# remoter.net
KiCad netlist of a schematic drawn in Altium Designer
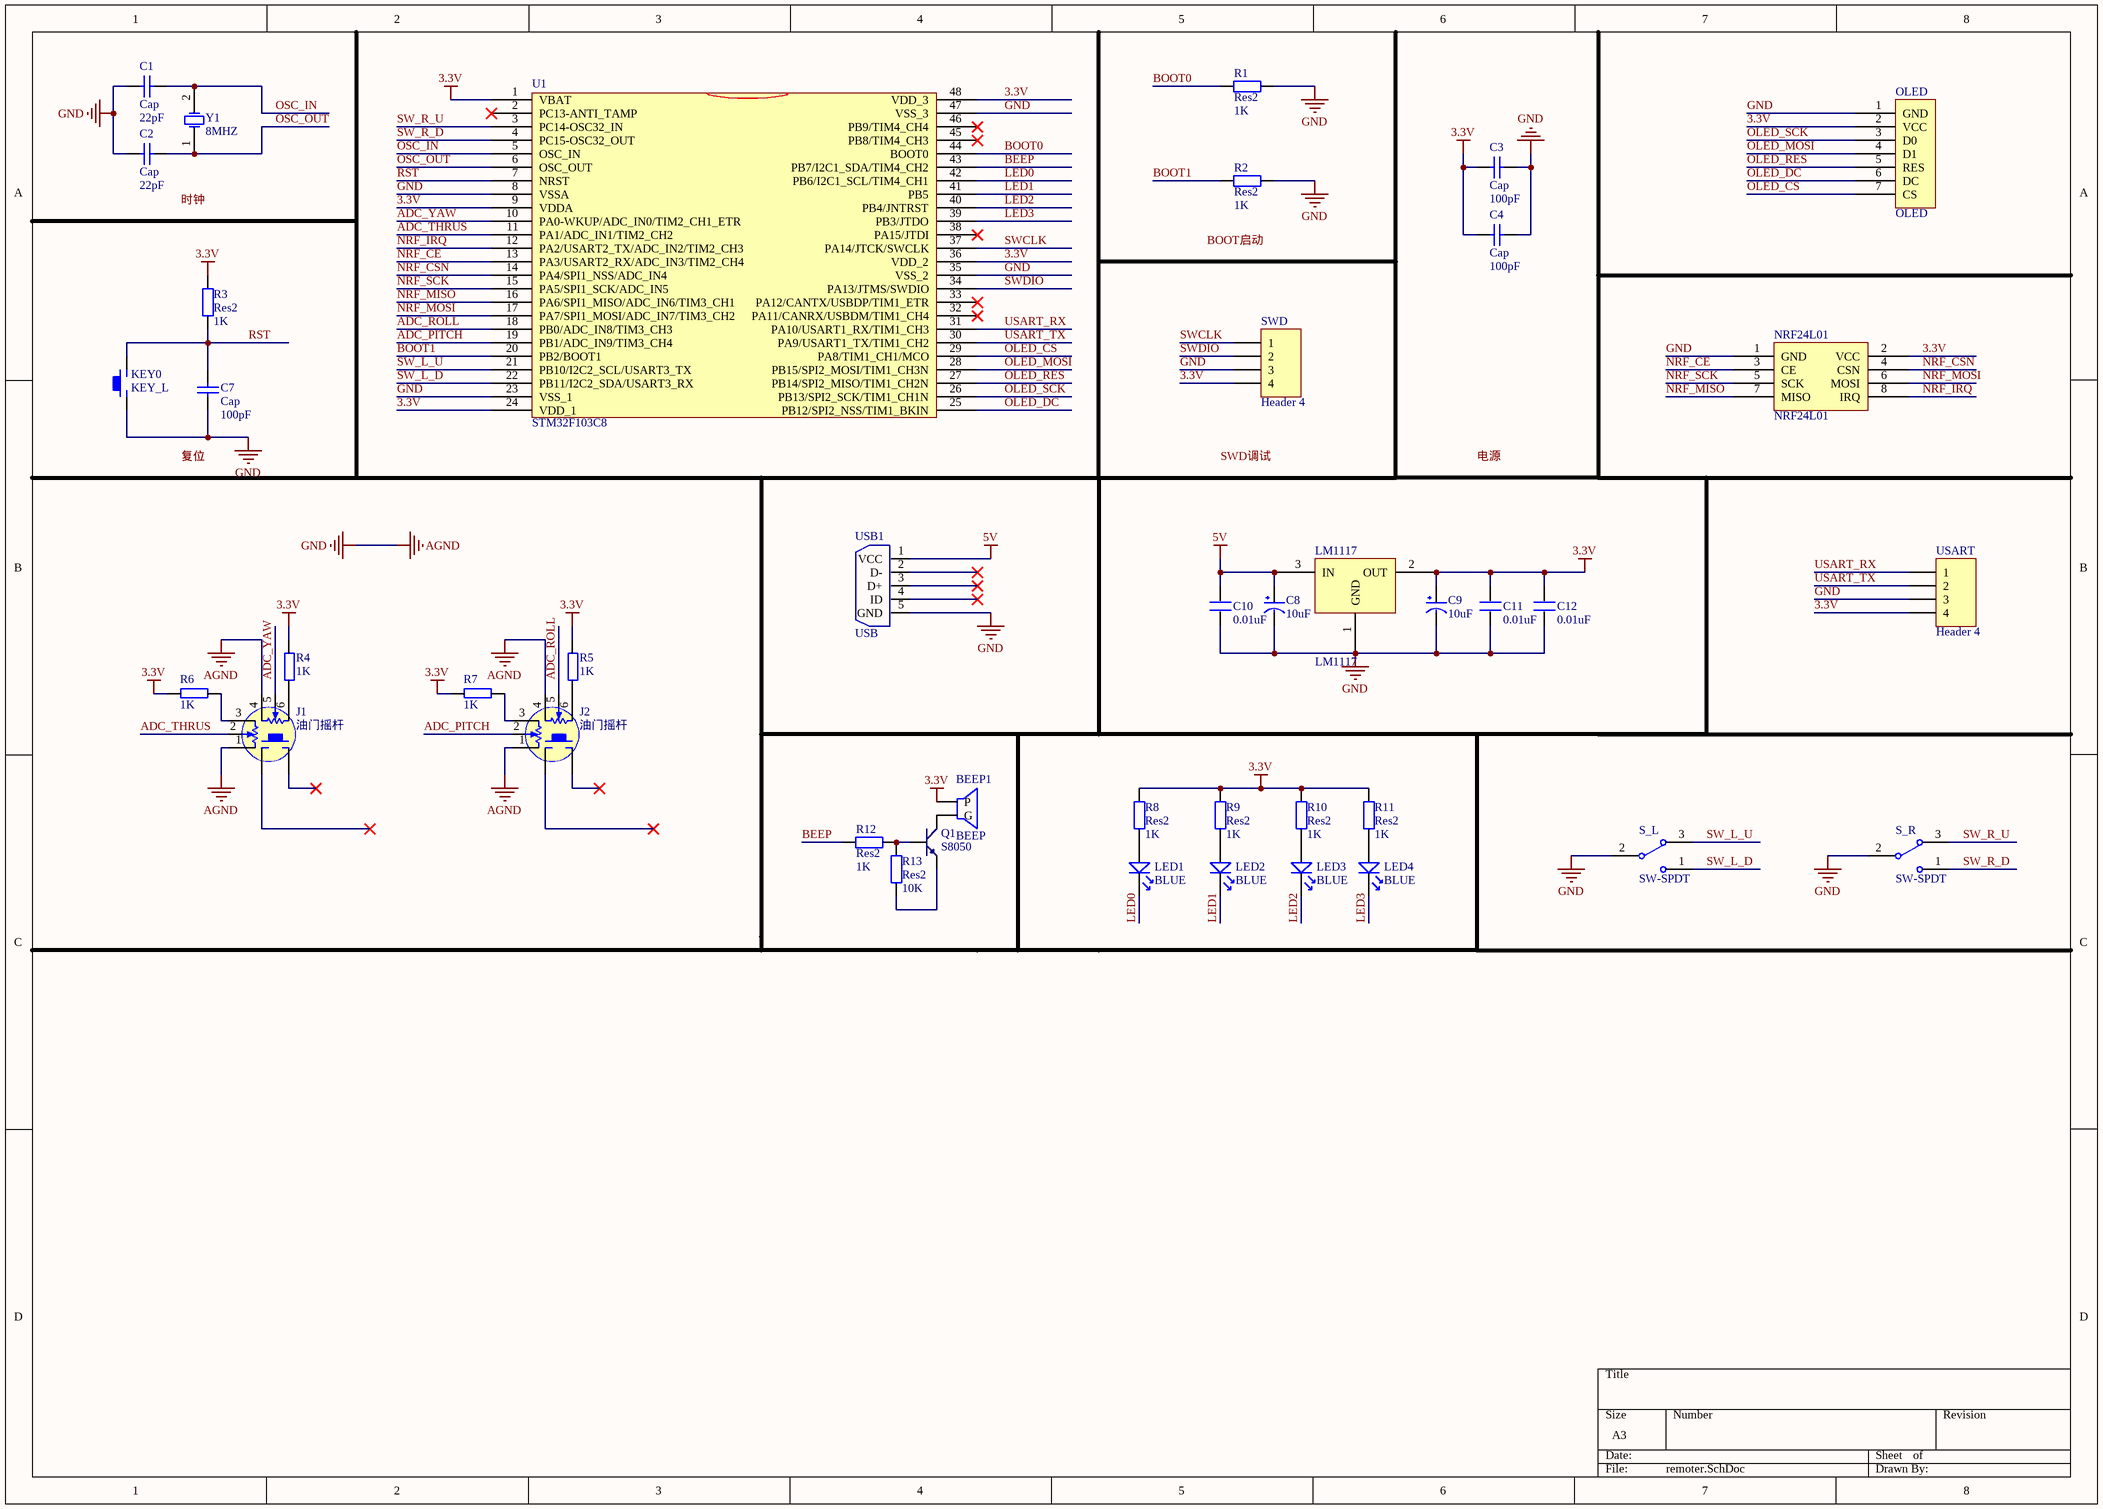
[diagram p0: remoter.SchDoc]

(export (version "E")
  (design (tool "Eeschema 10.0.6"))
  (components
    (comp (ref "BEEP1") (value "BEEP") (footprint "BELL-5") (libsource (lib "REMOTOR V1.6") (part "BEEP")))
    (comp (ref "C1")
      (value "Cap")
      (footprint "0805")
      (description "Capacitor")
      (fields (field (name "ALTIUM_VALUE") "22pF") (field (name "PUBLISHER") "Altium Limited"))
      (libsource (lib "Miscellaneous Devices") (part "Cap"))
    )
    (comp (ref "C2")
      (value "Cap")
      (footprint "0805")
      (description "Capacitor")
      (fields (field (name "ALTIUM_VALUE") "22pF") (field (name "PUBLISHER") "Altium Limited"))
      (libsource (lib "Miscellaneous Devices") (part "Cap"))
    )
    (comp (ref "C3")
      (value "Cap")
      (footprint "0805")
      (description "Capacitor")
      (fields (field (name "ALTIUM_VALUE") "100pF") (field (name "PUBLISHER") "Altium Limited"))
      (libsource (lib "Miscellaneous Devices") (part "Cap"))
    )
    (comp (ref "C4")
      (value "Cap")
      (footprint "0805")
      (description "Capacitor")
      (fields (field (name "ALTIUM_VALUE") "100pF") (field (name "PUBLISHER") "Altium Limited"))
      (libsource (lib "Miscellaneous Devices") (part "Cap"))
    )
    (comp (ref "C7")
      (value "Cap")
      (footprint "0805")
      (description "Capacitor")
      (fields (field (name "ALTIUM_VALUE") "100pF") (field (name "PUBLISHER") "Altium Limited"))
      (libsource (lib "Miscellaneous Devices") (part "Cap"))
    )
    (comp (ref "C8") (value "10uF") (footprint "C1206") (libsource (lib "REMOTOR V1.6") (part "CAP")))
    (comp (ref "C9") (value "10uF") (footprint "C1206") (libsource (lib "REMOTOR V1.6") (part "CAP")))
    (comp (ref "C10") (value "0.01uF") (footprint "0805") (libsource (lib "REMOTOR V1.6") (part "C")))
    (comp (ref "C11") (value "0.01uF") (footprint "0805") (libsource (lib "REMOTOR V1.6") (part "C")))
    (comp (ref "C12") (value "0.01uF") (footprint "0805") (libsource (lib "REMOTOR V1.6") (part "C")))
    (comp (ref "J1")
      (value "油门摇杆")
      (footprint "摇杆2")
      (description "摇杆")
      (libsource (lib "REMOTOR V1.6") (part "摇杆"))
    )
    (comp (ref "J2")
      (value "油门摇杆")
      (footprint "摇杆2")
      (description "摇杆")
      (libsource (lib "REMOTOR V1.6") (part "摇杆"))
    )
    (comp (ref "KEY0") (value "KEY_L") (footprint "KEY_M") (libsource (lib "REMOTOR V1.6") (part "KEY")))
    (comp (ref "LED1") (value "BLUE") (footprint "0805") (libsource (lib "REMOTOR V1.6") (part "LED")))
    (comp (ref "LED2") (value "BLUE") (footprint "0805") (libsource (lib "REMOTOR V1.6") (part "LED")))
    (comp (ref "LED3") (value "BLUE") (footprint "0805") (libsource (lib "REMOTOR V1.6") (part "LED")))
    (comp (ref "LED4") (value "BLUE") (footprint "0805") (libsource (lib "REMOTOR V1.6") (part "LED")))
    (comp (ref "LM1117")
      (value "LM1117")
      (description "线性稳压3.3V")
      (libsource (lib "Remoschlib") (part "LM1117"))
    )
    (comp (ref "NRF24L01")
      (value "NRF24L01")
      (footprint "HDR2X4")
      (libsource (lib "Remoschlib") (part "NRF24L01"))
    )
    (comp (ref "OLED") (value "OLED") (footprint "HDR1X7") (libsource (lib "Remoschlib") (part "OLED")))
    (comp (ref "Q1")
      (value "S8050")
      (footprint "SOT-23R")
      (description "8050/BCW846/BCW847")
      (libsource (lib "REMOTOR V1.6") (part "NPN"))
    )
    (comp (ref "R1")
      (value "Res2")
      (footprint "0805")
      (description "Resistor")
      (fields (field (name "ALTIUM_VALUE") "1K") (field (name "PUBLISHER") "Altium Limited"))
      (libsource (lib "") (part "Res2_2"))
    )
    (comp (ref "R2")
      (value "Res2")
      (footprint "0805")
      (description "Resistor")
      (fields (field (name "ALTIUM_VALUE") "1K") (field (name "PUBLISHER") "Altium Limited"))
      (libsource (lib "Miscellaneous Devices") (part "Res2"))
    )
    (comp (ref "R3")
      (value "Res2")
      (footprint "0805")
      (description "Resistor")
      (fields (field (name "ALTIUM_VALUE") "1K") (field (name "PUBLISHER") "Altium Limited"))
      (libsource (lib "") (part "Res2_1"))
    )
    (comp (ref "R4") (value "1K") (footprint "0805") (libsource (lib "REMOTOR V1.6") (part "R")))
    (comp (ref "R5") (value "1K") (footprint "0805") (libsource (lib "REMOTOR V1.6") (part "R")))
    (comp (ref "R6") (value "1K") (footprint "0805") (libsource (lib "REMOTOR V1.6") (part "R")))
    (comp (ref "R7") (value "1K") (footprint "0805") (libsource (lib "REMOTOR V1.6") (part "R")))
    (comp (ref "R8")
      (value "Res2")
      (footprint "0805")
      (description "Resistor")
      (fields (field (name "ALTIUM_VALUE") "1K") (field (name "PUBLISHER") "Altium Limited"))
      (libsource (lib "") (part "Res2_1"))
    )
    (comp (ref "R9")
      (value "Res2")
      (footprint "0805")
      (description "Resistor")
      (fields (field (name "ALTIUM_VALUE") "1K") (field (name "PUBLISHER") "Altium Limited"))
      (libsource (lib "") (part "Res2_1"))
    )
    (comp (ref "R10")
      (value "Res2")
      (footprint "0805")
      (description "Resistor")
      (fields (field (name "ALTIUM_VALUE") "1K") (field (name "PUBLISHER") "Altium Limited"))
      (libsource (lib "") (part "Res2_1"))
    )
    (comp (ref "R11")
      (value "Res2")
      (footprint "0805")
      (description "Resistor")
      (fields (field (name "ALTIUM_VALUE") "1K") (field (name "PUBLISHER") "Altium Limited"))
      (libsource (lib "") (part "Res2_1"))
    )
    (comp (ref "R12")
      (value "Res2")
      (footprint "0805")
      (description "Resistor")
      (fields (field (name "ALTIUM_VALUE") "1K") (field (name "PUBLISHER") "Altium Limited"))
      (libsource (lib "Miscellaneous Devices") (part "Res2"))
    )
    (comp (ref "R13")
      (value "Res2")
      (footprint "0805")
      (description "Resistor")
      (fields (field (name "ALTIUM_VALUE") "10K") (field (name "PUBLISHER") "Altium Limited"))
      (libsource (lib "") (part "Res2_1"))
    )
    (comp (ref "SWD")
      (value "Header 4")
      (footprint "HDR1X4")
      (description "Header, 4-Pin")
      (fields (field (name "PUBLISHER") "Altium Limited"))
      (libsource (lib "Miscellaneous Connectors") (part "Header 4"))
    )
    (comp (ref "S_L")
      (value "SW-SPDT")
      (footprint "扭子开关")
      (description "SPDT Subminiature Toggle Switch, Right Angle Mounting, Vertical Actuation")
      (fields (field (name "PUBLISHER") "Altium Limited"))
      (libsource (lib "Miscellaneous Devices") (part "SW-SPDT"))
    )
    (comp (ref "S_R")
      (value "SW-SPDT")
      (footprint "扭子开关")
      (description "SPDT Subminiature Toggle Switch, Right Angle Mounting, Vertical Actuation")
      (fields (field (name "PUBLISHER") "Altium Limited"))
      (libsource (lib "Miscellaneous Devices") (part "SW-SPDT"))
    )
    (comp (ref "U1")
      (value "STM32F103C8")
      (footprint "mTQFP48")
      (libsource (lib "REMOTOR V1.6") (part "STM32F103C6"))
    )
    (comp (ref "USART")
      (value "Header 4")
      (footprint "HDR1X4")
      (description "Header, 4-Pin")
      (fields (field (name "PUBLISHER") "Altium Limited"))
      (libsource (lib "Miscellaneous Connectors") (part "Header 4"))
    )
    (comp (ref "USB1")
      (value "USB")
      (footprint "MICROUSB-SOP")
      (libsource (lib "REMOTOR V1.6") (part "USB5"))
    )
    (comp (ref "Y1")
      (value "8MHZ")
      (footprint "XTAL3225   无源")
      (description "Crystal Oscillator")
      (fields (field (name "PUBLISHER") "Altium Limited"))
      (libsource (lib "Miscellaneous Devices") (part "XTAL"))
    )
  )
  (nets
    (net (code "1") (name "/ADC_PITCH") (class "Default")
      (node (ref "J2") (pin "2") (pinfunction "2_2") (pintype "passive"))
      (node (ref "U1") (pin "19") (pinfunction "PB1/ADC_IN9/TIM3_CH4_19") (pintype "passive"))
    )
    (net (code "2") (name "/ADC_ROLL") (class "Default")
      (node (ref "J2") (pin "5") (pinfunction "5_5") (pintype "passive"))
      (node (ref "U1") (pin "18") (pinfunction "PB0/ADC_IN8/TIM3_CH3_18") (pintype "passive"))
    )
    (net (code "3") (name "/ADC_THRUS") (class "Default")
      (node (ref "J1") (pin "2") (pinfunction "2_2") (pintype "passive"))
      (node (ref "U1") (pin "11") (pinfunction "PA1/ADC_IN1/TIM2_CH2_11") (pintype "passive"))
    )
    (net (code "4") (name "/ADC_YAW") (class "Default")
      (node (ref "J1") (pin "5") (pinfunction "5_5") (pintype "passive"))
      (node (ref "U1") (pin "10") (pinfunction "PA0-WKUP/ADC_IN0/TIM2_CH1_ETR_10") (pintype "passive"))
    )
    (net (code "5") (name "/BEEP") (class "Default")
      (node (ref "R12") (pin "2") (pinfunction "2_2") (pintype "passive"))
      (node (ref "U1") (pin "43") (pinfunction "PB7/I2C1_SDA/TIM4_CH2_43") (pintype "passive"))
    )
    (net (code "6") (name "/BOOT0") (class "Default")
      (node (ref "R1") (pin "1") (pinfunction "1_1") (pintype "passive"))
      (node (ref "U1") (pin "44") (pinfunction "BOOT0_44") (pintype "passive"))
    )
    (net (code "7") (name "/BOOT1") (class "Default")
      (node (ref "R2") (pin "2") (pinfunction "2_2") (pintype "passive"))
      (node (ref "U1") (pin "20") (pinfunction "PB2/BOOT1_20") (pintype "passive"))
    )
    (net (code "8") (name "/LED0") (class "Default")
      (node (ref "LED1") (pin "2") (pinfunction "2_2") (pintype "passive"))
      (node (ref "U1") (pin "42") (pinfunction "PB6/I2C1_SCL/TIM4_CH1_42") (pintype "passive"))
    )
    (net (code "9") (name "/LED1") (class "Default")
      (node (ref "LED2") (pin "2") (pinfunction "2_2") (pintype "passive"))
      (node (ref "U1") (pin "41") (pinfunction "PB5_41") (pintype "passive"))
    )
    (net (code "10") (name "/LED2") (class "Default")
      (node (ref "LED3") (pin "2") (pinfunction "2_2") (pintype "passive"))
      (node (ref "U1") (pin "40") (pinfunction "PB4/JNTRST_40") (pintype "passive"))
    )
    (net (code "11") (name "/LED3") (class "Default")
      (node (ref "LED4") (pin "2") (pinfunction "2_2") (pintype "passive"))
      (node (ref "U1") (pin "39") (pinfunction "PB3/JTDO_39") (pintype "passive"))
    )
    (net (code "12") (name "/NRF_CE") (class "Default")
      (node (ref "NRF24L01") (pin "3") (pinfunction "CE_3") (pintype "passive"))
      (node (ref "U1") (pin "13") (pinfunction "PA3/USART2_RX/ADC_IN3/TIM2_CH4_13") (pintype "passive"))
    )
    (net (code "13") (name "/NRF_CSN") (class "Default")
      (node (ref "NRF24L01") (pin "4") (pinfunction "CSN_4") (pintype "passive"))
      (node (ref "U1") (pin "14") (pinfunction "PA4/SPI1_NSS/ADC_IN4_14") (pintype "passive"))
    )
    (net (code "14") (name "/NRF_IRQ") (class "Default")
      (node (ref "NRF24L01") (pin "8") (pinfunction "IRQ_8") (pintype "passive"))
      (node (ref "U1") (pin "12") (pinfunction "PA2/USART2_TX/ADC_IN2/TIM2_CH3_12") (pintype "passive"))
    )
    (net (code "15") (name "/NRF_MISO") (class "Default")
      (node (ref "NRF24L01") (pin "7") (pinfunction "MISO_7") (pintype "passive"))
      (node (ref "U1") (pin "16") (pinfunction "PA6/SPI1_MISO/ADC_IN6/TIM3_CH1_16") (pintype "passive"))
    )
    (net (code "16") (name "/NRF_MOSI") (class "Default")
      (node (ref "NRF24L01") (pin "6") (pinfunction "MOSI_6") (pintype "passive"))
      (node (ref "U1") (pin "17") (pinfunction "PA7/SPI1_MOSI/ADC_IN7/TIM3_CH2_17") (pintype "passive"))
    )
    (net (code "17") (name "/NRF_SCK") (class "Default")
      (node (ref "NRF24L01") (pin "5") (pinfunction "SCK_5") (pintype "passive"))
      (node (ref "U1") (pin "15") (pinfunction "PA5/SPI1_SCK/ADC_IN5_15") (pintype "passive"))
    )
    (net (code "18") (name "/OLED_CS") (class "Default")
      (node (ref "OLED") (pin "7") (pinfunction "CS_7") (pintype "passive"))
      (node (ref "U1") (pin "29") (pinfunction "PA8/TIM1_CH1/MCO_29") (pintype "passive"))
    )
    (net (code "19") (name "/OLED_DC") (class "Default")
      (node (ref "OLED") (pin "6") (pinfunction "DC_6") (pintype "passive"))
      (node (ref "U1") (pin "25") (pinfunction "PB12/SPI2_NSS/TIM1_BKIN_25") (pintype "passive"))
    )
    (net (code "20") (name "/OLED_MOSI") (class "Default")
      (node (ref "OLED") (pin "4") (pinfunction "D1_4") (pintype "passive"))
      (node (ref "U1") (pin "28") (pinfunction "PB15/SPI2_MOSI/TIM1_CH3N_28") (pintype "passive"))
    )
    (net (code "21") (name "/OLED_RES") (class "Default")
      (node (ref "OLED") (pin "5") (pinfunction "RES_5") (pintype "passive"))
      (node (ref "U1") (pin "27") (pinfunction "PB14/SPI2_MISO/TIM1_CH2N_27") (pintype "passive"))
    )
    (net (code "22") (name "/OLED_SCK") (class "Default")
      (node (ref "OLED") (pin "3") (pinfunction "D0_3") (pintype "passive"))
      (node (ref "U1") (pin "26") (pinfunction "PB13/SPI2_SCK/TIM1_CH1N_26") (pintype "passive"))
    )
    (net (code "23") (name "/OSC_IN") (class "Default")
      (node (ref "C1") (pin "2") (pinfunction "2_2") (pintype "passive"))
      (node (ref "U1") (pin "5") (pinfunction "OSC_IN_5") (pintype "passive"))
      (node (ref "Y1") (pin "2") (pinfunction "OSC2_2") (pintype "passive"))
    )
    (net (code "24") (name "/OSC_OUT") (class "Default")
      (node (ref "C2") (pin "2") (pinfunction "2_2") (pintype "passive"))
      (node (ref "U1") (pin "6") (pinfunction "OSC_OUT_6") (pintype "passive"))
      (node (ref "Y1") (pin "1") (pinfunction "OSC1_1") (pintype "passive"))
    )
    (net (code "25") (name "/RST") (class "Default")
      (node (ref "C7") (pin "2") (pinfunction "2_2") (pintype "passive"))
      (node (ref "KEY0") (pin "2") (pinfunction "2_2") (pintype "passive"))
      (node (ref "R3") (pin "1") (pinfunction "1_1") (pintype "passive"))
      (node (ref "U1") (pin "7") (pinfunction "NRST_7") (pintype "passive"))
    )
    (net (code "26") (name "/SWCLK") (class "Default")
      (node (ref "SWD") (pin "1") (pinfunction "1_1") (pintype "passive"))
      (node (ref "U1") (pin "37") (pinfunction "PA14/JTCK/SWCLK_37") (pintype "passive"))
    )
    (net (code "27") (name "/SWDIO") (class "Default")
      (node (ref "SWD") (pin "2") (pinfunction "2_2") (pintype "passive"))
      (node (ref "U1") (pin "34") (pinfunction "PA13/JTMS/SWDIO_34") (pintype "passive"))
    )
    (net (code "28") (name "/SW_L_D") (class "Default")
      (node (ref "S_L") (pin "1") (pinfunction "1_1") (pintype "passive"))
      (node (ref "U1") (pin "22") (pinfunction "PB11/I2C2_SDA/USART3_RX_22") (pintype "passive"))
    )
    (net (code "29") (name "/SW_L_U") (class "Default")
      (node (ref "S_L") (pin "3") (pinfunction "3_3") (pintype "passive"))
      (node (ref "U1") (pin "21") (pinfunction "PB10/I2C2_SCL/USART3_TX_21") (pintype "passive"))
    )
    (net (code "30") (name "/SW_R_D") (class "Default")
      (node (ref "S_R") (pin "1") (pinfunction "1_1") (pintype "passive"))
      (node (ref "U1") (pin "4") (pinfunction "PC15-OSC32_OUT_4") (pintype "passive"))
    )
    (net (code "31") (name "/SW_R_U") (class "Default")
      (node (ref "S_R") (pin "3") (pinfunction "3_3") (pintype "passive"))
      (node (ref "U1") (pin "3") (pinfunction "PC14-OSC32_IN_3") (pintype "passive"))
    )
    (net (code "32") (name "/USART_RX") (class "Default")
      (node (ref "U1") (pin "31") (pinfunction "PA10/USART1_RX/TIM1_CH3_31") (pintype "passive"))
      (node (ref "USART") (pin "1") (pinfunction "1_1") (pintype "passive"))
    )
    (net (code "33") (name "/USART_TX") (class "Default")
      (node (ref "U1") (pin "30") (pinfunction "PA9/USART1_TX/TIM1_CH2_30") (pintype "passive"))
      (node (ref "USART") (pin "2") (pinfunction "2_2") (pintype "passive"))
    )
    (net (code "34") (name "3.3V") (class "Default")
      (node (ref "BEEP1") (pin "1") (pinfunction "P_1") (pintype "passive"))
      (node (ref "C11") (pin "2") (pintype "passive"))
      (node (ref "C12") (pin "2") (pintype "passive"))
      (node (ref "C3") (pin "1") (pinfunction "1_1") (pintype "passive"))
      (node (ref "C4") (pin "1") (pinfunction "1_1") (pintype "passive"))
      (node (ref "C9") (pin "1") (pinfunction "VCC_1") (pintype "passive"))
      (node (ref "LM1117") (pin "2") (pinfunction "OUT_2") (pintype "passive"))
      (node (ref "NRF24L01") (pin "2") (pinfunction "VCC_2") (pintype "passive"))
      (node (ref "OLED") (pin "2") (pinfunction "VCC_2") (pintype "passive"))
      (node (ref "R10") (pin "2") (pinfunction "2_2") (pintype "passive"))
      (node (ref "R11") (pin "2") (pinfunction "2_2") (pintype "passive"))
      (node (ref "R3") (pin "2") (pinfunction "2_2") (pintype "passive"))
      (node (ref "R4") (pin "2") (pintype "passive"))
      (node (ref "R5") (pin "2") (pintype "passive"))
      (node (ref "R6") (pin "2") (pintype "passive"))
      (node (ref "R7") (pin "2") (pintype "passive"))
      (node (ref "R8") (pin "2") (pinfunction "2_2") (pintype "passive"))
      (node (ref "R9") (pin "2") (pinfunction "2_2") (pintype "passive"))
      (node (ref "SWD") (pin "4") (pinfunction "4_4") (pintype "passive"))
      (node (ref "U1") (pin "1") (pinfunction "VBAT_1") (pintype "passive"))
      (node (ref "U1") (pin "24") (pinfunction "VDD_1_24") (pintype "passive"))
      (node (ref "U1") (pin "36") (pinfunction "VDD_2_36") (pintype "passive"))
      (node (ref "U1") (pin "48") (pinfunction "VDD_3_48") (pintype "passive"))
      (node (ref "U1") (pin "9") (pinfunction "VDDA_9") (pintype "passive"))
      (node (ref "USART") (pin "4") (pinfunction "4_4") (pintype "passive"))
    )
    (net (code "35") (name "5V") (class "Default")
      (node (ref "C10") (pin "2") (pintype "passive"))
      (node (ref "C8") (pin "1") (pinfunction "VCC_1") (pintype "passive"))
      (node (ref "LM1117") (pin "3") (pinfunction "IN_3") (pintype "passive"))
      (node (ref "USB1") (pin "1") (pinfunction "VCC_1") (pintype "passive"))
    )
    (net (code "36") (name "AGND") (class "Default")
      (node (ref "C1") (pin "1") (pinfunction "1_1") (pintype "passive"))
      (node (ref "C10") (pin "1") (pintype "passive"))
      (node (ref "C11") (pin "1") (pintype "passive"))
      (node (ref "C12") (pin "1") (pintype "passive"))
      (node (ref "C2") (pin "1") (pinfunction "1_1") (pintype "passive"))
      (node (ref "C3") (pin "2") (pinfunction "2_2") (pintype "passive"))
      (node (ref "C4") (pin "2") (pinfunction "2_2") (pintype "passive"))
      (node (ref "C7") (pin "1") (pinfunction "1_1") (pintype "passive"))
      (node (ref "C8") (pin "2") (pinfunction "GND_2") (pintype "passive"))
      (node (ref "C9") (pin "2") (pinfunction "GND_2") (pintype "passive"))
      (node (ref "J1") (pin "1") (pinfunction "1_1") (pintype "passive"))
      (node (ref "J1") (pin "4") (pinfunction "4_4") (pintype "passive"))
      (node (ref "J2") (pin "1") (pinfunction "1_1") (pintype "passive"))
      (node (ref "J2") (pin "4") (pinfunction "4_4") (pintype "passive"))
      (node (ref "KEY0") (pin "1") (pinfunction "1_1") (pintype "passive"))
      (node (ref "LM1117") (pin "1") (pinfunction "GND_1") (pintype "passive"))
      (node (ref "NRF24L01") (pin "1") (pinfunction "GND_1") (pintype "passive"))
      (node (ref "OLED") (pin "1") (pinfunction "GND_1") (pintype "passive"))
      (node (ref "R1") (pin "2") (pinfunction "2_2") (pintype "passive"))
      (node (ref "R2") (pin "1") (pinfunction "1_1") (pintype "passive"))
      (node (ref "SWD") (pin "3") (pinfunction "3_3") (pintype "passive"))
      (node (ref "S_L") (pin "2") (pinfunction "2_2") (pintype "passive"))
      (node (ref "S_R") (pin "2") (pinfunction "2_2") (pintype "passive"))
      (node (ref "U1") (pin "23") (pinfunction "VSS_1_23") (pintype "passive"))
      (node (ref "U1") (pin "35") (pinfunction "VSS_2_35") (pintype "passive"))
      (node (ref "U1") (pin "47") (pinfunction "VSS_3_47") (pintype "passive"))
      (node (ref "U1") (pin "8") (pinfunction "VSSA_8") (pintype "passive"))
      (node (ref "USART") (pin "3") (pinfunction "3_3") (pintype "passive"))
      (node (ref "USB1") (pin "5") (pinfunction "GND_5") (pintype "passive"))
    )
    (net (code "37") (name "Net-(BEEP1-G)") (class "Default")
      (node (ref "BEEP1") (pin "2") (pinfunction "G_2") (pintype "passive"))
      (node (ref "Q1") (pin "3") (pinfunction "C_3") (pintype "passive"))
    )
    (net (code "38") (name "Net-(J1-Pad3)") (class "Default")
      (node (ref "J1") (pin "3") (pinfunction "3_3") (pintype "passive"))
      (node (ref "R6") (pin "1") (pintype "passive"))
    )
    (net (code "39") (name "Net-(J1-Pad6)") (class "Default")
      (node (ref "J1") (pin "6") (pinfunction "6_6") (pintype "passive"))
      (node (ref "R4") (pin "1") (pintype "passive"))
    )
    (net (code "40") (name "Net-(J2-Pad3)") (class "Default")
      (node (ref "J2") (pin "3") (pinfunction "3_3") (pintype "passive"))
      (node (ref "R7") (pin "1") (pintype "passive"))
    )
    (net (code "41") (name "Net-(J2-Pad6)") (class "Default")
      (node (ref "J2") (pin "6") (pinfunction "6_6") (pintype "passive"))
      (node (ref "R5") (pin "1") (pintype "passive"))
    )
    (net (code "42") (name "Net-(LED1-Pad1)") (class "Default")
      (node (ref "LED1") (pin "1") (pinfunction "1_1") (pintype "passive"))
      (node (ref "R8") (pin "1") (pinfunction "1_1") (pintype "passive"))
    )
    (net (code "43") (name "Net-(LED2-Pad1)") (class "Default")
      (node (ref "LED2") (pin "1") (pinfunction "1_1") (pintype "passive"))
      (node (ref "R9") (pin "1") (pinfunction "1_1") (pintype "passive"))
    )
    (net (code "44") (name "Net-(LED3-Pad1)") (class "Default")
      (node (ref "LED3") (pin "1") (pinfunction "1_1") (pintype "passive"))
      (node (ref "R10") (pin "1") (pinfunction "1_1") (pintype "passive"))
    )
    (net (code "45") (name "Net-(LED4-Pad1)") (class "Default")
      (node (ref "LED4") (pin "1") (pinfunction "1_1") (pintype "passive"))
      (node (ref "R11") (pin "1") (pinfunction "1_1") (pintype "passive"))
    )
    (net (code "46") (name "Net-(Q1-B)") (class "Default")
      (node (ref "Q1") (pin "2") (pinfunction "B_2") (pintype "passive"))
      (node (ref "R12") (pin "1") (pinfunction "1_1") (pintype "passive"))
      (node (ref "R13") (pin "2") (pinfunction "2_2") (pintype "passive"))
    )
    (net (code "47") (name "Net-(Q1-E)") (class "Default")
      (node (ref "Q1") (pin "1") (pinfunction "E_1") (pintype "passive"))
      (node (ref "R13") (pin "1") (pinfunction "1_1") (pintype "passive"))
    )
    (net (code "48") (name "unconnected-(J1-PadJ1)") (class "Default")
      (node (ref "J1") (pin "J1") (pinfunction "J1_J1") (pintype "passive+no_connect"))
    )
    (net (code "49") (name "unconnected-(J1-PadJ2)") (class "Default")
      (node (ref "J1") (pin "J2") (pinfunction "J2_J2") (pintype "passive+no_connect"))
    )
    (net (code "50") (name "unconnected-(J2-PadJ1)") (class "Default")
      (node (ref "J2") (pin "J1") (pinfunction "J1_J1") (pintype "passive+no_connect"))
    )
    (net (code "51") (name "unconnected-(J2-PadJ2)") (class "Default")
      (node (ref "J2") (pin "J2") (pinfunction "J2_J2") (pintype "passive+no_connect"))
    )
    (net (code "52") (name "unconnected-(U1-PA11{slash}CANRX{slash}USBDM{slash}TIM1_CH4-Pad32)") (class "Default")
      (node (ref "U1") (pin "32") (pinfunction "PA11/CANRX/USBDM/TIM1_CH4_32") (pintype "passive+no_connect"))
    )
    (net (code "53") (name "unconnected-(U1-PA12{slash}CANTX{slash}USBDP{slash}TIM1_ETR-Pad33)") (class "Default")
      (node (ref "U1") (pin "33") (pinfunction "PA12/CANTX/USBDP/TIM1_ETR_33") (pintype "passive+no_connect"))
    )
    (net (code "54") (name "unconnected-(U1-PA15{slash}JTDI-Pad38)") (class "Default")
      (node (ref "U1") (pin "38") (pinfunction "PA15/JTDI_38") (pintype "passive+no_connect"))
    )
    (net (code "55") (name "unconnected-(U1-PB8{slash}TIM4_CH3-Pad45)") (class "Default")
      (node (ref "U1") (pin "45") (pinfunction "PB8/TIM4_CH3_45") (pintype "passive+no_connect"))
    )
    (net (code "56") (name "unconnected-(U1-PB9{slash}TIM4_CH4-Pad46)") (class "Default")
      (node (ref "U1") (pin "46") (pinfunction "PB9/TIM4_CH4_46") (pintype "passive+no_connect"))
    )
    (net (code "57") (name "unconnected-(U1-PC13-ANTI_TAMP-Pad2)") (class "Default")
      (node (ref "U1") (pin "2") (pinfunction "PC13-ANTI_TAMP_2") (pintype "passive+no_connect"))
    )
    (net (code "58") (name "unconnected-(USB1-D+-Pad3)") (class "Default")
      (node (ref "USB1") (pin "3") (pinfunction "D+_3") (pintype "passive+no_connect"))
    )
    (net (code "59") (name "unconnected-(USB1-D--Pad2)") (class "Default")
      (node (ref "USB1") (pin "2") (pinfunction "D-_2") (pintype "passive+no_connect"))
    )
    (net (code "60") (name "unconnected-(USB1-ID-Pad4)") (class "Default")
      (node (ref "USB1") (pin "4") (pinfunction "ID_4") (pintype "passive+no_connect"))
    )
  )
)
